# pc_kalam_ads1220_cap.net
KiCad netlist of a schematic drawn in EAGLE
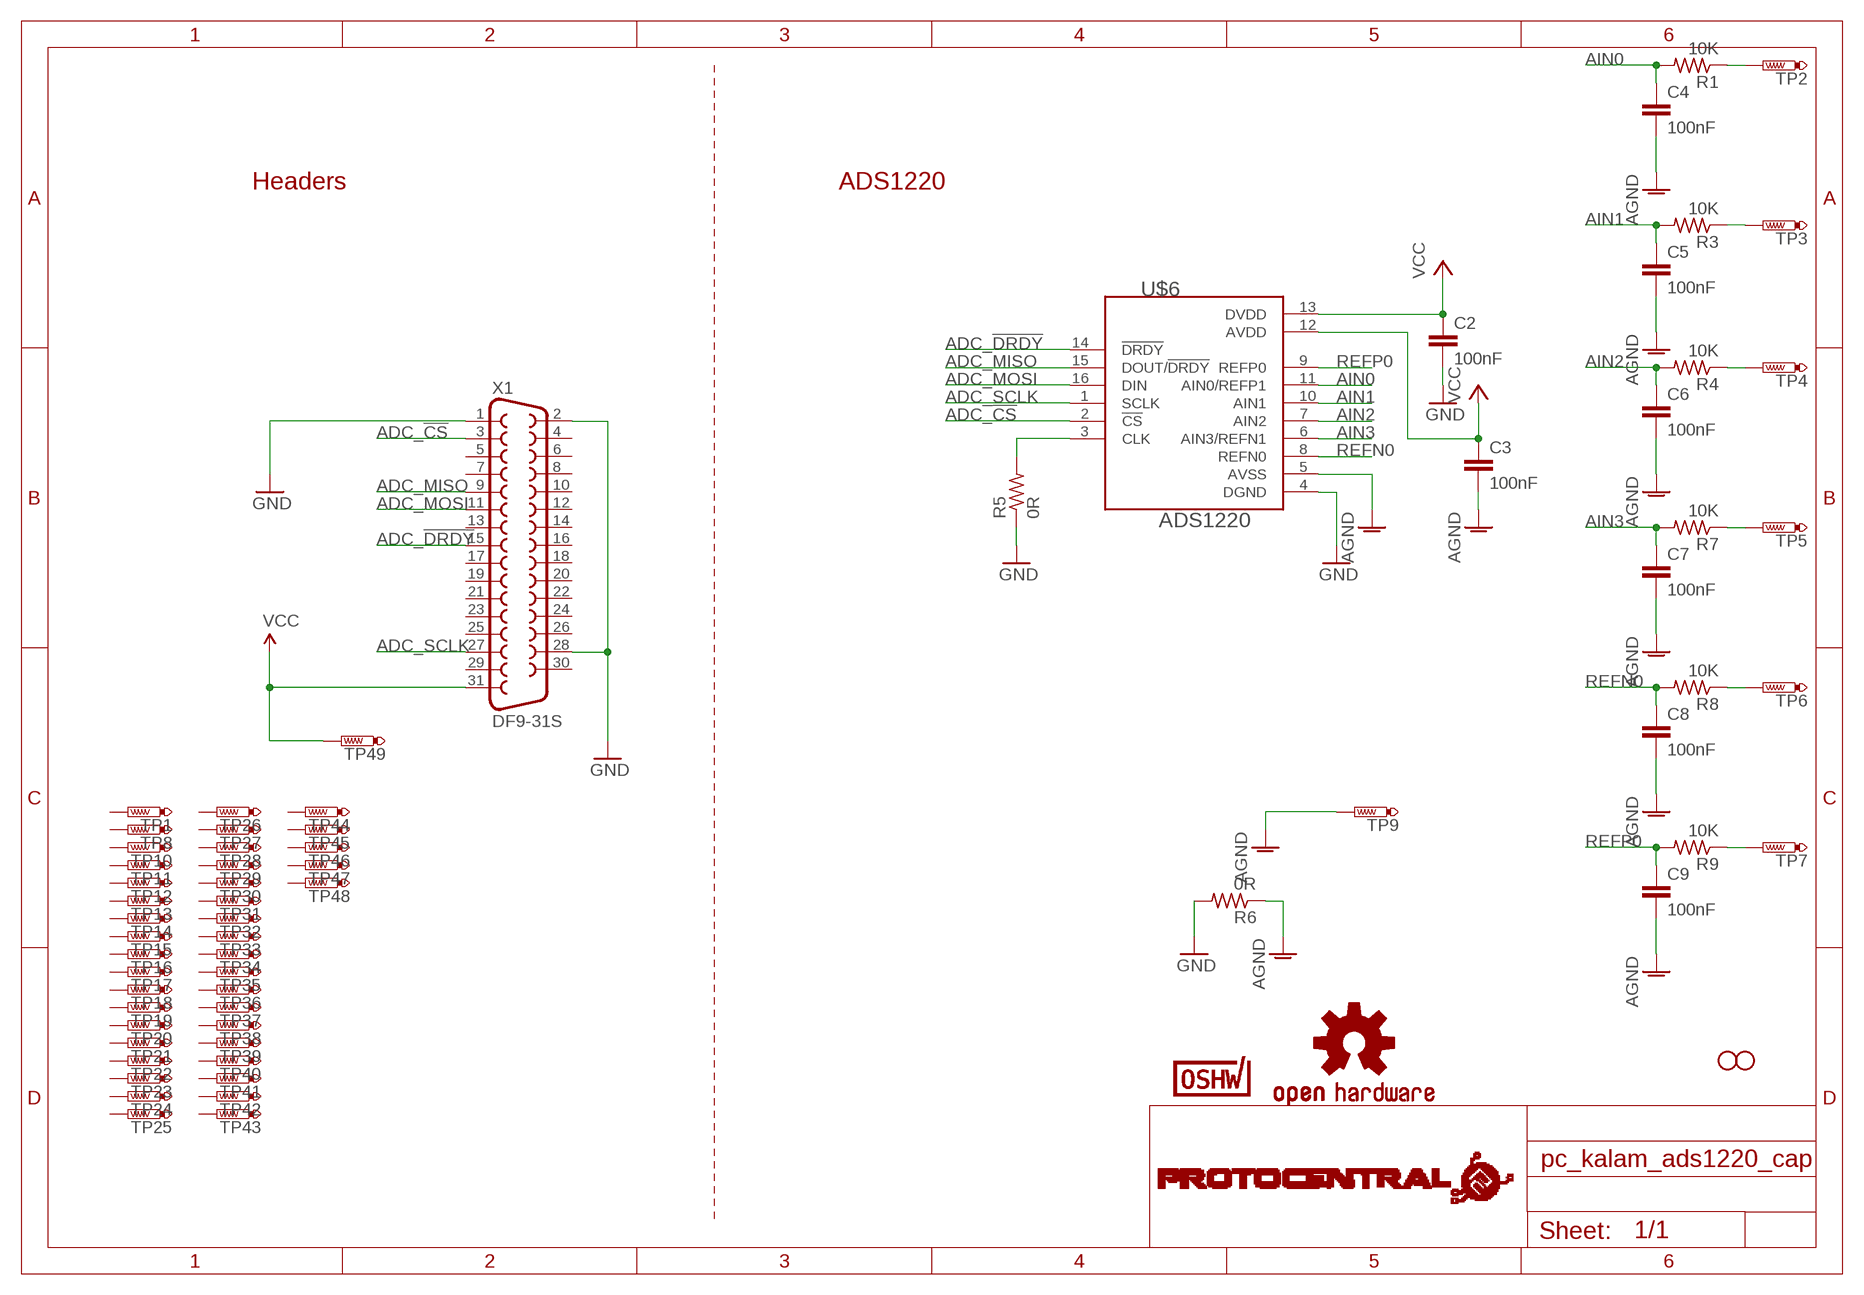
[diagram p0: schematic, sheet 1]

(export (version "E")
  (design (tool "Eeschema 10.0.6"))
  (components
    (comp (ref "C2")
      (value "100nF")
      (footprint "eagle-import:C0805")
      (libsource (lib "eagle-import") (part "C-EUC0805"))
    )
    (comp (ref "C3")
      (value "100nF")
      (footprint "eagle-import:C0805")
      (libsource (lib "eagle-import") (part "C-EUC0805"))
    )
    (comp (ref "C4")
      (value "100nF")
      (footprint "eagle-import:C0805")
      (libsource (lib "eagle-import") (part "C-EUC0805"))
    )
    (comp (ref "C5")
      (value "100nF")
      (footprint "eagle-import:C0805")
      (libsource (lib "eagle-import") (part "C-EUC0805"))
    )
    (comp (ref "C6")
      (value "100nF")
      (footprint "eagle-import:C0805")
      (libsource (lib "eagle-import") (part "C-EUC0805"))
    )
    (comp (ref "C7")
      (value "100nF")
      (footprint "eagle-import:C0805")
      (libsource (lib "eagle-import") (part "C-EUC0805"))
    )
    (comp (ref "C8")
      (value "100nF")
      (footprint "eagle-import:C0805")
      (libsource (lib "eagle-import") (part "C-EUC0805"))
    )
    (comp (ref "C9")
      (value "100nF")
      (footprint "eagle-import:C0805")
      (libsource (lib "eagle-import") (part "C-EUC0805"))
    )
    (comp (ref "R1")
      (value "10K")
      (footprint "eagle-import:R0805")
      (libsource (lib "eagle-import") (part "R-US_R0805"))
    )
    (comp (ref "R3")
      (value "10K")
      (footprint "eagle-import:R0805")
      (libsource (lib "eagle-import") (part "R-US_R0805"))
    )
    (comp (ref "R4")
      (value "10K")
      (footprint "eagle-import:R0805")
      (libsource (lib "eagle-import") (part "R-US_R0805"))
    )
    (comp (ref "R5")
      (value "0R")
      (footprint "eagle-import:R0805")
      (libsource (lib "eagle-import") (part "R-US_R0805"))
    )
    (comp (ref "R6")
      (value "0R")
      (footprint "eagle-import:R0805")
      (libsource (lib "eagle-import") (part "R-US_R0805"))
    )
    (comp (ref "R7")
      (value "10K")
      (footprint "eagle-import:R0805")
      (libsource (lib "eagle-import") (part "R-US_R0805"))
    )
    (comp (ref "R8")
      (value "10K")
      (footprint "eagle-import:R0805")
      (libsource (lib "eagle-import") (part "R-US_R0805"))
    )
    (comp (ref "R9")
      (value "10K")
      (footprint "eagle-import:R0805")
      (libsource (lib "eagle-import") (part "R-US_R0805"))
    )
    (comp (ref "STANDOFF7")
      (value "STAND-OFF")
      (footprint "eagle-import:STAND-OFF")
      (libsource (lib "eagle-import") (part "STAND-OFF"))
    )
    (comp (ref "STANDOFF8")
      (value "STAND-OFF")
      (footprint "eagle-import:STAND-OFF")
      (libsource (lib "eagle-import") (part "STAND-OFF"))
    )
    (comp (ref "TP1")
      (value "PTR1PAD1-13")
      (footprint "eagle-import:P1-13")
      (libsource (lib "eagle-import") (part "PTR1PAD1-13"))
    )
    (comp (ref "TP2")
      (value "PTR1PAD1-13")
      (footprint "eagle-import:P1-13")
      (libsource (lib "eagle-import") (part "PTR1PAD1-13"))
    )
    (comp (ref "TP3")
      (value "PTR1PAD1-13")
      (footprint "eagle-import:P1-13")
      (libsource (lib "eagle-import") (part "PTR1PAD1-13"))
    )
    (comp (ref "TP4")
      (value "PTR1PAD1-13")
      (footprint "eagle-import:P1-13")
      (libsource (lib "eagle-import") (part "PTR1PAD1-13"))
    )
    (comp (ref "TP5")
      (value "PTR1PAD1-13")
      (footprint "eagle-import:P1-13")
      (libsource (lib "eagle-import") (part "PTR1PAD1-13"))
    )
    (comp (ref "TP6")
      (value "PTR1PAD1-13")
      (footprint "eagle-import:P1-13")
      (libsource (lib "eagle-import") (part "PTR1PAD1-13"))
    )
    (comp (ref "TP7")
      (value "PTR1PAD1-13")
      (footprint "eagle-import:P1-13")
      (libsource (lib "eagle-import") (part "PTR1PAD1-13"))
    )
    (comp (ref "TP8")
      (value "PTR1PAD1-13")
      (footprint "eagle-import:P1-13")
      (libsource (lib "eagle-import") (part "PTR1PAD1-13"))
    )
    (comp (ref "TP9")
      (value "PTR1PAD1-13")
      (footprint "eagle-import:P1-13")
      (libsource (lib "eagle-import") (part "PTR1PAD1-13"))
    )
    (comp (ref "TP10")
      (value "PTR1PAD1-13")
      (footprint "eagle-import:P1-13")
      (libsource (lib "eagle-import") (part "PTR1PAD1-13"))
    )
    (comp (ref "TP11")
      (value "PTR1PAD1-13")
      (footprint "eagle-import:P1-13")
      (libsource (lib "eagle-import") (part "PTR1PAD1-13"))
    )
    (comp (ref "TP12")
      (value "PTR1PAD1-13")
      (footprint "eagle-import:P1-13")
      (libsource (lib "eagle-import") (part "PTR1PAD1-13"))
    )
    (comp (ref "TP13")
      (value "PTR1PAD1-13")
      (footprint "eagle-import:P1-13")
      (libsource (lib "eagle-import") (part "PTR1PAD1-13"))
    )
    (comp (ref "TP14")
      (value "PTR1PAD1-13")
      (footprint "eagle-import:P1-13")
      (libsource (lib "eagle-import") (part "PTR1PAD1-13"))
    )
    (comp (ref "TP15")
      (value "PTR1PAD1-13")
      (footprint "eagle-import:P1-13")
      (libsource (lib "eagle-import") (part "PTR1PAD1-13"))
    )
    (comp (ref "TP16")
      (value "PTR1PAD1-13")
      (footprint "eagle-import:P1-13")
      (libsource (lib "eagle-import") (part "PTR1PAD1-13"))
    )
    (comp (ref "TP17")
      (value "PTR1PAD1-13")
      (footprint "eagle-import:P1-13")
      (libsource (lib "eagle-import") (part "PTR1PAD1-13"))
    )
    (comp (ref "TP18")
      (value "PTR1PAD1-13")
      (footprint "eagle-import:P1-13")
      (libsource (lib "eagle-import") (part "PTR1PAD1-13"))
    )
    (comp (ref "TP19")
      (value "PTR1PAD1-13")
      (footprint "eagle-import:P1-13")
      (libsource (lib "eagle-import") (part "PTR1PAD1-13"))
    )
    (comp (ref "TP20")
      (value "PTR1PAD1-13")
      (footprint "eagle-import:P1-13")
      (libsource (lib "eagle-import") (part "PTR1PAD1-13"))
    )
    (comp (ref "TP21")
      (value "PTR1PAD1-13")
      (footprint "eagle-import:P1-13")
      (libsource (lib "eagle-import") (part "PTR1PAD1-13"))
    )
    (comp (ref "TP22")
      (value "PTR1PAD1-13")
      (footprint "eagle-import:P1-13")
      (libsource (lib "eagle-import") (part "PTR1PAD1-13"))
    )
    (comp (ref "TP23")
      (value "PTR1PAD1-13")
      (footprint "eagle-import:P1-13")
      (libsource (lib "eagle-import") (part "PTR1PAD1-13"))
    )
    (comp (ref "TP24")
      (value "PTR1PAD1-13")
      (footprint "eagle-import:P1-13")
      (libsource (lib "eagle-import") (part "PTR1PAD1-13"))
    )
    (comp (ref "TP25")
      (value "PTR1PAD1-13")
      (footprint "eagle-import:P1-13")
      (libsource (lib "eagle-import") (part "PTR1PAD1-13"))
    )
    (comp (ref "TP26")
      (value "PTR1PAD1-13")
      (footprint "eagle-import:P1-13")
      (libsource (lib "eagle-import") (part "PTR1PAD1-13"))
    )
    (comp (ref "TP27")
      (value "PTR1PAD1-13")
      (footprint "eagle-import:P1-13")
      (libsource (lib "eagle-import") (part "PTR1PAD1-13"))
    )
    (comp (ref "TP28")
      (value "PTR1PAD1-13")
      (footprint "eagle-import:P1-13")
      (libsource (lib "eagle-import") (part "PTR1PAD1-13"))
    )
    (comp (ref "TP29")
      (value "PTR1PAD1-13")
      (footprint "eagle-import:P1-13")
      (libsource (lib "eagle-import") (part "PTR1PAD1-13"))
    )
    (comp (ref "TP30")
      (value "PTR1PAD1-13")
      (footprint "eagle-import:P1-13")
      (libsource (lib "eagle-import") (part "PTR1PAD1-13"))
    )
    (comp (ref "TP31")
      (value "PTR1PAD1-13")
      (footprint "eagle-import:P1-13")
      (libsource (lib "eagle-import") (part "PTR1PAD1-13"))
    )
    (comp (ref "TP32")
      (value "PTR1PAD1-13")
      (footprint "eagle-import:P1-13")
      (libsource (lib "eagle-import") (part "PTR1PAD1-13"))
    )
    (comp (ref "TP33")
      (value "PTR1PAD1-13")
      (footprint "eagle-import:P1-13")
      (libsource (lib "eagle-import") (part "PTR1PAD1-13"))
    )
    (comp (ref "TP34")
      (value "PTR1PAD1-13")
      (footprint "eagle-import:P1-13")
      (libsource (lib "eagle-import") (part "PTR1PAD1-13"))
    )
    (comp (ref "TP35")
      (value "PTR1PAD1-13")
      (footprint "eagle-import:P1-13")
      (libsource (lib "eagle-import") (part "PTR1PAD1-13"))
    )
    (comp (ref "TP36")
      (value "PTR1PAD1-13")
      (footprint "eagle-import:P1-13")
      (libsource (lib "eagle-import") (part "PTR1PAD1-13"))
    )
    (comp (ref "TP37")
      (value "PTR1PAD1-13")
      (footprint "eagle-import:P1-13")
      (libsource (lib "eagle-import") (part "PTR1PAD1-13"))
    )
    (comp (ref "TP38")
      (value "PTR1PAD1-13")
      (footprint "eagle-import:P1-13")
      (libsource (lib "eagle-import") (part "PTR1PAD1-13"))
    )
    (comp (ref "TP39")
      (value "PTR1PAD1-13")
      (footprint "eagle-import:P1-13")
      (libsource (lib "eagle-import") (part "PTR1PAD1-13"))
    )
    (comp (ref "TP40")
      (value "PTR1PAD1-13")
      (footprint "eagle-import:P1-13")
      (libsource (lib "eagle-import") (part "PTR1PAD1-13"))
    )
    (comp (ref "TP41")
      (value "PTR1PAD1-13")
      (footprint "eagle-import:P1-13")
      (libsource (lib "eagle-import") (part "PTR1PAD1-13"))
    )
    (comp (ref "TP42")
      (value "PTR1PAD1-13")
      (footprint "eagle-import:P1-13")
      (libsource (lib "eagle-import") (part "PTR1PAD1-13"))
    )
    (comp (ref "TP43")
      (value "PTR1PAD1-13")
      (footprint "eagle-import:P1-13")
      (libsource (lib "eagle-import") (part "PTR1PAD1-13"))
    )
    (comp (ref "TP44")
      (value "PTR1PAD1-13")
      (footprint "eagle-import:P1-13")
      (libsource (lib "eagle-import") (part "PTR1PAD1-13"))
    )
    (comp (ref "TP45")
      (value "PTR1PAD1-13")
      (footprint "eagle-import:P1-13")
      (libsource (lib "eagle-import") (part "PTR1PAD1-13"))
    )
    (comp (ref "TP46")
      (value "PTR1PAD1-13")
      (footprint "eagle-import:P1-13")
      (libsource (lib "eagle-import") (part "PTR1PAD1-13"))
    )
    (comp (ref "TP47")
      (value "PTR1PAD1-13")
      (footprint "eagle-import:P1-13")
      (libsource (lib "eagle-import") (part "PTR1PAD1-13"))
    )
    (comp (ref "TP48")
      (value "PTR1PAD1-13")
      (footprint "eagle-import:P1-13")
      (libsource (lib "eagle-import") (part "PTR1PAD1-13"))
    )
    (comp (ref "TP49")
      (value "PTR1PAD1-13")
      (footprint "eagle-import:P1-13")
      (libsource (lib "eagle-import") (part "PTR1PAD1-13"))
    )
    (comp (ref "U$1")
      (value "PROTY-LOGO")
      (footprint "eagle-import:LOGO-PROTY")
      (libsource (lib "eagle-import") (part "PROTY-LOGO"))
    )
    (comp (ref "U$2")
      (value "CERT-SMALL")
      (footprint "eagle-import:CERT-SMALL-SILK")
      (libsource (lib "eagle-import") (part "CERT-SMALL"))
    )
    (comp (ref "U$3")
      (value "OSHW-LOGOS")
      (footprint "eagle-import:OSHW-LOGO-S")
      (libsource (lib "eagle-import") (part "OSHW-LOGOS"))
    )
    (comp (ref "U$6")
      (value "ADS1220")
      (footprint "eagle-import:TSSOP-16")
      (libsource (lib "eagle-import") (part "ADS1220"))
    )
    (comp (ref "X1")
      (value "DF9-31S")
      (footprint "eagle-import:DF9-31S")
      (fields (field (name "MPN") "DF9-31S-1V(32)"))
      (libsource (lib "eagle-import") (part "DF9-31S"))
    )
  )
  (nets
    (net (code "1") (name "/ADC_MISO") (class "Default")
      (node (ref "U$6") (pin "15") (pinfunction "DOUT/~{DRDY}_15") (pintype "bidirectional"))
      (node (ref "X1") (pin "9") (pinfunction "9_9") (pintype "passive"))
    )
    (net (code "2") (name "/ADC_MOSI") (class "Default")
      (node (ref "U$6") (pin "16") (pinfunction "DIN_16") (pintype "bidirectional"))
      (node (ref "X1") (pin "11") (pinfunction "11_11") (pintype "passive"))
    )
    (net (code "3") (name "/ADC_SCLK") (class "Default")
      (node (ref "U$6") (pin "1") (pinfunction "SCLK_1") (pintype "bidirectional"))
      (node (ref "X1") (pin "27") (pinfunction "27_27") (pintype "passive"))
    )
    (net (code "4") (name "/ADC_~{CS}") (class "Default")
      (node (ref "U$6") (pin "2") (pinfunction "~{CS}_2") (pintype "bidirectional"))
      (node (ref "X1") (pin "3") (pinfunction "3_3") (pintype "passive"))
    )
    (net (code "5") (name "/ADC_~{DRDY}") (class "Default")
      (node (ref "U$6") (pin "14") (pinfunction "~{DRDY}_14") (pintype "bidirectional"))
      (node (ref "X1") (pin "15") (pinfunction "15_15") (pintype "passive"))
    )
    (net (code "6") (name "/AIN0") (class "Default")
      (node (ref "C4") (pin "1") (pinfunction "1_1") (pintype "passive"))
      (node (ref "R1") (pin "2") (pinfunction "2_2") (pintype "passive"))
      (node (ref "U$6") (pin "11") (pinfunction "AIN0/REFP1_11") (pintype "bidirectional"))
    )
    (net (code "7") (name "/AIN1") (class "Default")
      (node (ref "C5") (pin "1") (pinfunction "1_1") (pintype "passive"))
      (node (ref "R3") (pin "2") (pinfunction "2_2") (pintype "passive"))
      (node (ref "U$6") (pin "10") (pinfunction "AIN1_10") (pintype "bidirectional"))
    )
    (net (code "8") (name "/AIN2") (class "Default")
      (node (ref "C6") (pin "1") (pinfunction "1_1") (pintype "passive"))
      (node (ref "R4") (pin "2") (pinfunction "2_2") (pintype "passive"))
      (node (ref "U$6") (pin "7") (pinfunction "AIN2_7") (pintype "bidirectional"))
    )
    (net (code "9") (name "/AIN3") (class "Default")
      (node (ref "C7") (pin "1") (pinfunction "1_1") (pintype "passive"))
      (node (ref "R7") (pin "2") (pinfunction "2_2") (pintype "passive"))
      (node (ref "U$6") (pin "6") (pinfunction "AIN3/REFN1_6") (pintype "bidirectional"))
    )
    (net (code "10") (name "/REFN0") (class "Default")
      (node (ref "C8") (pin "1") (pinfunction "1_1") (pintype "passive"))
      (node (ref "R8") (pin "2") (pinfunction "2_2") (pintype "passive"))
      (node (ref "U$6") (pin "8") (pinfunction "REFN0_8") (pintype "bidirectional"))
    )
    (net (code "11") (name "/REFP0") (class "Default")
      (node (ref "C9") (pin "1") (pinfunction "1_1") (pintype "passive"))
      (node (ref "R9") (pin "2") (pinfunction "2_2") (pintype "passive"))
      (node (ref "U$6") (pin "9") (pinfunction "REFP0_9") (pintype "bidirectional"))
    )
    (net (code "12") (name "AGND") (class "Default")
      (node (ref "C3") (pin "2") (pinfunction "2_2") (pintype "passive"))
      (node (ref "C4") (pin "2") (pinfunction "2_2") (pintype "passive"))
      (node (ref "C5") (pin "2") (pinfunction "2_2") (pintype "passive"))
      (node (ref "C6") (pin "2") (pinfunction "2_2") (pintype "passive"))
      (node (ref "C7") (pin "2") (pinfunction "2_2") (pintype "passive"))
      (node (ref "C8") (pin "2") (pinfunction "2_2") (pintype "passive"))
      (node (ref "C9") (pin "2") (pinfunction "2_2") (pintype "passive"))
      (node (ref "R6") (pin "1") (pinfunction "1_1") (pintype "passive"))
      (node (ref "TP9") (pin "TP") (pinfunction "TP_TP") (pintype "input"))
      (node (ref "U$6") (pin "5") (pinfunction "AVSS_5") (pintype "bidirectional"))
    )
    (net (code "13") (name "GND") (class "Default")
      (node (ref "C2") (pin "2") (pinfunction "2_2") (pintype "passive"))
      (node (ref "R5") (pin "1") (pinfunction "1_1") (pintype "passive"))
      (node (ref "R6") (pin "2") (pinfunction "2_2") (pintype "passive"))
      (node (ref "U$6") (pin "4") (pinfunction "DGND_4") (pintype "bidirectional"))
      (node (ref "X1") (pin "1") (pinfunction "1_1") (pintype "passive"))
      (node (ref "X1") (pin "2") (pinfunction "2_2") (pintype "passive"))
      (node (ref "X1") (pin "28") (pinfunction "28_28") (pintype "passive"))
    )
    (net (code "14") (name "Net-(R1-Pad1)") (class "Default")
      (node (ref "R1") (pin "1") (pinfunction "1_1") (pintype "passive"))
      (node (ref "TP2") (pin "TP") (pinfunction "TP_TP") (pintype "input"))
    )
    (net (code "15") (name "Net-(R3-Pad1)") (class "Default")
      (node (ref "R3") (pin "1") (pinfunction "1_1") (pintype "passive"))
      (node (ref "TP3") (pin "TP") (pinfunction "TP_TP") (pintype "input"))
    )
    (net (code "16") (name "Net-(R4-Pad1)") (class "Default")
      (node (ref "R4") (pin "1") (pinfunction "1_1") (pintype "passive"))
      (node (ref "TP4") (pin "TP") (pinfunction "TP_TP") (pintype "input"))
    )
    (net (code "17") (name "Net-(R7-Pad1)") (class "Default")
      (node (ref "R7") (pin "1") (pinfunction "1_1") (pintype "passive"))
      (node (ref "TP5") (pin "TP") (pinfunction "TP_TP") (pintype "input"))
    )
    (net (code "18") (name "Net-(R8-Pad1)") (class "Default")
      (node (ref "R8") (pin "1") (pinfunction "1_1") (pintype "passive"))
      (node (ref "TP6") (pin "TP") (pinfunction "TP_TP") (pintype "input"))
    )
    (net (code "19") (name "Net-(R9-Pad1)") (class "Default")
      (node (ref "R9") (pin "1") (pinfunction "1_1") (pintype "passive"))
      (node (ref "TP7") (pin "TP") (pinfunction "TP_TP") (pintype "input"))
    )
    (net (code "20") (name "Net-(U$6-CLK)") (class "Default")
      (node (ref "R5") (pin "2") (pinfunction "2_2") (pintype "passive"))
      (node (ref "U$6") (pin "3") (pinfunction "CLK_3") (pintype "bidirectional"))
    )
    (net (code "21") (name "VCC") (class "Default")
      (node (ref "C2") (pin "1") (pinfunction "1_1") (pintype "passive"))
      (node (ref "C3") (pin "1") (pinfunction "1_1") (pintype "passive"))
      (node (ref "TP49") (pin "TP") (pinfunction "TP_TP") (pintype "input"))
      (node (ref "U$6") (pin "12") (pinfunction "AVDD_12") (pintype "bidirectional"))
      (node (ref "U$6") (pin "13") (pinfunction "DVDD_13") (pintype "bidirectional"))
      (node (ref "X1") (pin "31") (pinfunction "31_31") (pintype "passive"))
    )
    (net (code "22") (name "unconnected-(TP1-PadTP)") (class "Default")
      (node (ref "TP1") (pin "TP") (pinfunction "TP_TP") (pintype "input"))
    )
    (net (code "23") (name "unconnected-(TP8-PadTP)") (class "Default")
      (node (ref "TP8") (pin "TP") (pinfunction "TP_TP") (pintype "input"))
    )
    (net (code "24") (name "unconnected-(TP10-PadTP)") (class "Default")
      (node (ref "TP10") (pin "TP") (pinfunction "TP_TP") (pintype "input"))
    )
    (net (code "25") (name "unconnected-(TP11-PadTP)") (class "Default")
      (node (ref "TP11") (pin "TP") (pinfunction "TP_TP") (pintype "input"))
    )
    (net (code "26") (name "unconnected-(TP12-PadTP)") (class "Default")
      (node (ref "TP12") (pin "TP") (pinfunction "TP_TP") (pintype "input"))
    )
    (net (code "27") (name "unconnected-(TP13-PadTP)") (class "Default")
      (node (ref "TP13") (pin "TP") (pinfunction "TP_TP") (pintype "input"))
    )
    (net (code "28") (name "unconnected-(TP14-PadTP)") (class "Default")
      (node (ref "TP14") (pin "TP") (pinfunction "TP_TP") (pintype "input"))
    )
    (net (code "29") (name "unconnected-(TP15-PadTP)") (class "Default")
      (node (ref "TP15") (pin "TP") (pinfunction "TP_TP") (pintype "input"))
    )
    (net (code "30") (name "unconnected-(TP16-PadTP)") (class "Default")
      (node (ref "TP16") (pin "TP") (pinfunction "TP_TP") (pintype "input"))
    )
    (net (code "31") (name "unconnected-(TP17-PadTP)") (class "Default")
      (node (ref "TP17") (pin "TP") (pinfunction "TP_TP") (pintype "input"))
    )
    (net (code "32") (name "unconnected-(TP18-PadTP)") (class "Default")
      (node (ref "TP18") (pin "TP") (pinfunction "TP_TP") (pintype "input"))
    )
    (net (code "33") (name "unconnected-(TP19-PadTP)") (class "Default")
      (node (ref "TP19") (pin "TP") (pinfunction "TP_TP") (pintype "input"))
    )
    (net (code "34") (name "unconnected-(TP20-PadTP)") (class "Default")
      (node (ref "TP20") (pin "TP") (pinfunction "TP_TP") (pintype "input"))
    )
    (net (code "35") (name "unconnected-(TP21-PadTP)") (class "Default")
      (node (ref "TP21") (pin "TP") (pinfunction "TP_TP") (pintype "input"))
    )
    (net (code "36") (name "unconnected-(TP22-PadTP)") (class "Default")
      (node (ref "TP22") (pin "TP") (pinfunction "TP_TP") (pintype "input"))
    )
    (net (code "37") (name "unconnected-(TP23-PadTP)") (class "Default")
      (node (ref "TP23") (pin "TP") (pinfunction "TP_TP") (pintype "input"))
    )
    (net (code "38") (name "unconnected-(TP24-PadTP)") (class "Default")
      (node (ref "TP24") (pin "TP") (pinfunction "TP_TP") (pintype "input"))
    )
    (net (code "39") (name "unconnected-(TP25-PadTP)") (class "Default")
      (node (ref "TP25") (pin "TP") (pinfunction "TP_TP") (pintype "input"))
    )
    (net (code "40") (name "unconnected-(TP26-PadTP)") (class "Default")
      (node (ref "TP26") (pin "TP") (pinfunction "TP_TP") (pintype "input"))
    )
    (net (code "41") (name "unconnected-(TP27-PadTP)") (class "Default")
      (node (ref "TP27") (pin "TP") (pinfunction "TP_TP") (pintype "input"))
    )
    (net (code "42") (name "unconnected-(TP28-PadTP)") (class "Default")
      (node (ref "TP28") (pin "TP") (pinfunction "TP_TP") (pintype "input"))
    )
    (net (code "43") (name "unconnected-(TP29-PadTP)") (class "Default")
      (node (ref "TP29") (pin "TP") (pinfunction "TP_TP") (pintype "input"))
    )
    (net (code "44") (name "unconnected-(TP30-PadTP)") (class "Default")
      (node (ref "TP30") (pin "TP") (pinfunction "TP_TP") (pintype "input"))
    )
    (net (code "45") (name "unconnected-(TP31-PadTP)") (class "Default")
      (node (ref "TP31") (pin "TP") (pinfunction "TP_TP") (pintype "input"))
    )
    (net (code "46") (name "unconnected-(TP32-PadTP)") (class "Default")
      (node (ref "TP32") (pin "TP") (pinfunction "TP_TP") (pintype "input"))
    )
    (net (code "47") (name "unconnected-(TP33-PadTP)") (class "Default")
      (node (ref "TP33") (pin "TP") (pinfunction "TP_TP") (pintype "input"))
    )
    (net (code "48") (name "unconnected-(TP34-PadTP)") (class "Default")
      (node (ref "TP34") (pin "TP") (pinfunction "TP_TP") (pintype "input"))
    )
    (net (code "49") (name "unconnected-(TP35-PadTP)") (class "Default")
      (node (ref "TP35") (pin "TP") (pinfunction "TP_TP") (pintype "input"))
    )
    (net (code "50") (name "unconnected-(TP36-PadTP)") (class "Default")
      (node (ref "TP36") (pin "TP") (pinfunction "TP_TP") (pintype "input"))
    )
    (net (code "51") (name "unconnected-(TP37-PadTP)") (class "Default")
      (node (ref "TP37") (pin "TP") (pinfunction "TP_TP") (pintype "input"))
    )
    (net (code "52") (name "unconnected-(TP38-PadTP)") (class "Default")
      (node (ref "TP38") (pin "TP") (pinfunction "TP_TP") (pintype "input"))
    )
    (net (code "53") (name "unconnected-(TP39-PadTP)") (class "Default")
      (node (ref "TP39") (pin "TP") (pinfunction "TP_TP") (pintype "input"))
    )
    (net (code "54") (name "unconnected-(TP40-PadTP)") (class "Default")
      (node (ref "TP40") (pin "TP") (pinfunction "TP_TP") (pintype "input"))
    )
    (net (code "55") (name "unconnected-(TP41-PadTP)") (class "Default")
      (node (ref "TP41") (pin "TP") (pinfunction "TP_TP") (pintype "input"))
    )
    (net (code "56") (name "unconnected-(TP42-PadTP)") (class "Default")
      (node (ref "TP42") (pin "TP") (pinfunction "TP_TP") (pintype "input"))
    )
    (net (code "57") (name "unconnected-(TP43-PadTP)") (class "Default")
      (node (ref "TP43") (pin "TP") (pinfunction "TP_TP") (pintype "input"))
    )
    (net (code "58") (name "unconnected-(TP44-PadTP)") (class "Default")
      (node (ref "TP44") (pin "TP") (pinfunction "TP_TP") (pintype "input"))
    )
    (net (code "59") (name "unconnected-(TP45-PadTP)") (class "Default")
      (node (ref "TP45") (pin "TP") (pinfunction "TP_TP") (pintype "input"))
    )
    (net (code "60") (name "unconnected-(TP46-PadTP)") (class "Default")
      (node (ref "TP46") (pin "TP") (pinfunction "TP_TP") (pintype "input"))
    )
    (net (code "61") (name "unconnected-(TP47-PadTP)") (class "Default")
      (node (ref "TP47") (pin "TP") (pinfunction "TP_TP") (pintype "input"))
    )
    (net (code "62") (name "unconnected-(TP48-PadTP)") (class "Default")
      (node (ref "TP48") (pin "TP") (pinfunction "TP_TP") (pintype "input"))
    )
    (net (code "63") (name "unconnected-(X1-Pad4)") (class "Default")
      (node (ref "X1") (pin "4") (pinfunction "4_4") (pintype "passive"))
    )
    (net (code "64") (name "unconnected-(X1-Pad5)") (class "Default")
      (node (ref "X1") (pin "5") (pinfunction "5_5") (pintype "passive"))
    )
    (net (code "65") (name "unconnected-(X1-Pad6)") (class "Default")
      (node (ref "X1") (pin "6") (pinfunction "6_6") (pintype "passive"))
    )
    (net (code "66") (name "unconnected-(X1-Pad7)") (class "Default")
      (node (ref "X1") (pin "7") (pinfunction "7_7") (pintype "passive"))
    )
    (net (code "67") (name "unconnected-(X1-Pad8)") (class "Default")
      (node (ref "X1") (pin "8") (pinfunction "8_8") (pintype "passive"))
    )
    (net (code "68") (name "unconnected-(X1-Pad10)") (class "Default")
      (node (ref "X1") (pin "10") (pinfunction "10_10") (pintype "passive"))
    )
    (net (code "69") (name "unconnected-(X1-Pad12)") (class "Default")
      (node (ref "X1") (pin "12") (pinfunction "12_12") (pintype "passive"))
    )
    (net (code "70") (name "unconnected-(X1-Pad13)") (class "Default")
      (node (ref "X1") (pin "13") (pinfunction "13_13") (pintype "passive"))
    )
    (net (code "71") (name "unconnected-(X1-Pad14)") (class "Default")
      (node (ref "X1") (pin "14") (pinfunction "14_14") (pintype "passive"))
    )
    (net (code "72") (name "unconnected-(X1-Pad16)") (class "Default")
      (node (ref "X1") (pin "16") (pinfunction "16_16") (pintype "passive"))
    )
    (net (code "73") (name "unconnected-(X1-Pad17)") (class "Default")
      (node (ref "X1") (pin "17") (pinfunction "17_17") (pintype "passive"))
    )
    (net (code "74") (name "unconnected-(X1-Pad18)") (class "Default")
      (node (ref "X1") (pin "18") (pinfunction "18_18") (pintype "passive"))
    )
    (net (code "75") (name "unconnected-(X1-Pad19)") (class "Default")
      (node (ref "X1") (pin "19") (pinfunction "19_19") (pintype "passive"))
    )
    (net (code "76") (name "unconnected-(X1-Pad20)") (class "Default")
      (node (ref "X1") (pin "20") (pinfunction "20_20") (pintype "passive"))
    )
    (net (code "77") (name "unconnected-(X1-Pad21)") (class "Default")
      (node (ref "X1") (pin "21") (pinfunction "21_21") (pintype "passive"))
    )
    (net (code "78") (name "unconnected-(X1-Pad22)") (class "Default")
      (node (ref "X1") (pin "22") (pinfunction "22_22") (pintype "passive"))
    )
    (net (code "79") (name "unconnected-(X1-Pad23)") (class "Default")
      (node (ref "X1") (pin "23") (pinfunction "23_23") (pintype "passive"))
    )
    (net (code "80") (name "unconnected-(X1-Pad24)") (class "Default")
      (node (ref "X1") (pin "24") (pinfunction "24_24") (pintype "passive"))
    )
    (net (code "81") (name "unconnected-(X1-Pad25)") (class "Default")
      (node (ref "X1") (pin "25") (pinfunction "25_25") (pintype "passive"))
    )
    (net (code "82") (name "unconnected-(X1-Pad26)") (class "Default")
      (node (ref "X1") (pin "26") (pinfunction "26_26") (pintype "passive"))
    )
    (net (code "83") (name "unconnected-(X1-Pad29)") (class "Default")
      (node (ref "X1") (pin "29") (pinfunction "29_29") (pintype "passive"))
    )
    (net (code "84") (name "unconnected-(X1-Pad30)") (class "Default")
      (node (ref "X1") (pin "30") (pinfunction "30_30") (pintype "passive"))
    )
  )
)
